# qPCR_pcb_module_array_led.net
KiCad netlist of a schematic drawn in EAGLE
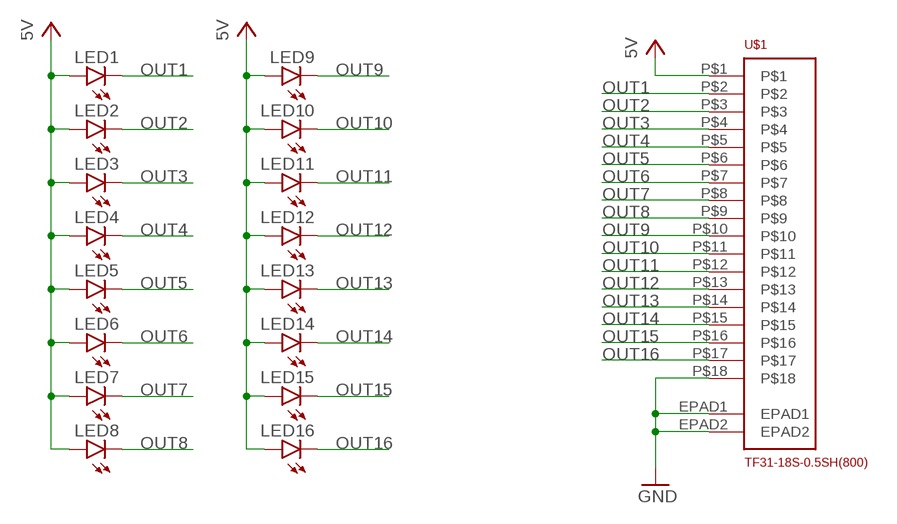
[diagram p0: schematic, sheet 1]

(export (version "E")
  (design (tool "Eeschema 10.0.6"))
  (components
    (comp (ref "LED1")
      (value "LED5MM")
      (footprint "eagle-import:LED5MM")
      (libsource (lib "eagle-import") (part "LED5MM"))
    )
    (comp (ref "LED2")
      (value "LED5MM")
      (footprint "eagle-import:LED5MM")
      (libsource (lib "eagle-import") (part "LED5MM"))
    )
    (comp (ref "LED3")
      (value "LED5MM")
      (footprint "eagle-import:LED5MM")
      (libsource (lib "eagle-import") (part "LED5MM"))
    )
    (comp (ref "LED4")
      (value "LED5MM")
      (footprint "eagle-import:LED5MM")
      (libsource (lib "eagle-import") (part "LED5MM"))
    )
    (comp (ref "LED5")
      (value "LED5MM")
      (footprint "eagle-import:LED5MM")
      (libsource (lib "eagle-import") (part "LED5MM"))
    )
    (comp (ref "LED6")
      (value "LED5MM")
      (footprint "eagle-import:LED5MM")
      (libsource (lib "eagle-import") (part "LED5MM"))
    )
    (comp (ref "LED7")
      (value "LED5MM")
      (footprint "eagle-import:LED5MM")
      (libsource (lib "eagle-import") (part "LED5MM"))
    )
    (comp (ref "LED8")
      (value "LED5MM")
      (footprint "eagle-import:LED5MM")
      (libsource (lib "eagle-import") (part "LED5MM"))
    )
    (comp (ref "LED9")
      (value "LED5MM")
      (footprint "eagle-import:LED5MM")
      (libsource (lib "eagle-import") (part "LED5MM"))
    )
    (comp (ref "LED10")
      (value "LED5MM")
      (footprint "eagle-import:LED5MM")
      (libsource (lib "eagle-import") (part "LED5MM"))
    )
    (comp (ref "LED11")
      (value "LED5MM")
      (footprint "eagle-import:LED5MM")
      (libsource (lib "eagle-import") (part "LED5MM"))
    )
    (comp (ref "LED12")
      (value "LED5MM")
      (footprint "eagle-import:LED5MM")
      (libsource (lib "eagle-import") (part "LED5MM"))
    )
    (comp (ref "LED13")
      (value "LED5MM")
      (footprint "eagle-import:LED5MM")
      (libsource (lib "eagle-import") (part "LED5MM"))
    )
    (comp (ref "LED14")
      (value "LED5MM")
      (footprint "eagle-import:LED5MM")
      (libsource (lib "eagle-import") (part "LED5MM"))
    )
    (comp (ref "LED15")
      (value "LED5MM")
      (footprint "eagle-import:LED5MM")
      (libsource (lib "eagle-import") (part "LED5MM"))
    )
    (comp (ref "LED16")
      (value "LED5MM")
      (footprint "eagle-import:LED5MM")
      (libsource (lib "eagle-import") (part "LED5MM"))
    )
    (comp (ref "U$1")
      (value "TF31-18S-0.5SH(800)")
      (footprint "eagle-import:TF31-18S-0.5SH(800)")
      (libsource (lib "eagle-import") (part "TF31-18S-0.5SH(800)"))
    )
  )
  (nets
    (net (code "1") (name "/OUT1") (class "Default")
      (node (ref "LED1") (pin "K") (pinfunction "C_K") (pintype "passive"))
      (node (ref "U$1") (pin "P$2") (pinfunction "P$2_P$2") (pintype "bidirectional"))
    )
    (net (code "2") (name "/OUT2") (class "Default")
      (node (ref "LED2") (pin "K") (pinfunction "C_K") (pintype "passive"))
      (node (ref "U$1") (pin "P$3") (pinfunction "P$3_P$3") (pintype "bidirectional"))
    )
    (net (code "3") (name "/OUT3") (class "Default")
      (node (ref "LED3") (pin "K") (pinfunction "C_K") (pintype "passive"))
      (node (ref "U$1") (pin "P$4") (pinfunction "P$4_P$4") (pintype "bidirectional"))
    )
    (net (code "4") (name "/OUT4") (class "Default")
      (node (ref "LED4") (pin "K") (pinfunction "C_K") (pintype "passive"))
      (node (ref "U$1") (pin "P$5") (pinfunction "P$5_P$5") (pintype "bidirectional"))
    )
    (net (code "5") (name "/OUT5") (class "Default")
      (node (ref "LED5") (pin "K") (pinfunction "C_K") (pintype "passive"))
      (node (ref "U$1") (pin "P$6") (pinfunction "P$6_P$6") (pintype "bidirectional"))
    )
    (net (code "6") (name "/OUT6") (class "Default")
      (node (ref "LED6") (pin "K") (pinfunction "C_K") (pintype "passive"))
      (node (ref "U$1") (pin "P$7") (pinfunction "P$7_P$7") (pintype "bidirectional"))
    )
    (net (code "7") (name "/OUT7") (class "Default")
      (node (ref "LED7") (pin "K") (pinfunction "C_K") (pintype "passive"))
      (node (ref "U$1") (pin "P$8") (pinfunction "P$8_P$8") (pintype "bidirectional"))
    )
    (net (code "8") (name "/OUT8") (class "Default")
      (node (ref "LED8") (pin "K") (pinfunction "C_K") (pintype "passive"))
      (node (ref "U$1") (pin "P$9") (pinfunction "P$9_P$9") (pintype "bidirectional"))
    )
    (net (code "9") (name "/OUT9") (class "Default")
      (node (ref "LED9") (pin "K") (pinfunction "C_K") (pintype "passive"))
      (node (ref "U$1") (pin "P$10") (pinfunction "P$10_P$10") (pintype "bidirectional"))
    )
    (net (code "10") (name "/OUT10") (class "Default")
      (node (ref "LED10") (pin "K") (pinfunction "C_K") (pintype "passive"))
      (node (ref "U$1") (pin "P$11") (pinfunction "P$11_P$11") (pintype "bidirectional"))
    )
    (net (code "11") (name "/OUT11") (class "Default")
      (node (ref "LED11") (pin "K") (pinfunction "C_K") (pintype "passive"))
      (node (ref "U$1") (pin "P$12") (pinfunction "P$12_P$12") (pintype "bidirectional"))
    )
    (net (code "12") (name "/OUT12") (class "Default")
      (node (ref "LED12") (pin "K") (pinfunction "C_K") (pintype "passive"))
      (node (ref "U$1") (pin "P$13") (pinfunction "P$13_P$13") (pintype "bidirectional"))
    )
    (net (code "13") (name "/OUT13") (class "Default")
      (node (ref "LED13") (pin "K") (pinfunction "C_K") (pintype "passive"))
      (node (ref "U$1") (pin "P$14") (pinfunction "P$14_P$14") (pintype "bidirectional"))
    )
    (net (code "14") (name "/OUT14") (class "Default")
      (node (ref "LED14") (pin "K") (pinfunction "C_K") (pintype "passive"))
      (node (ref "U$1") (pin "P$15") (pinfunction "P$15_P$15") (pintype "bidirectional"))
    )
    (net (code "15") (name "/OUT15") (class "Default")
      (node (ref "LED15") (pin "K") (pinfunction "C_K") (pintype "passive"))
      (node (ref "U$1") (pin "P$16") (pinfunction "P$16_P$16") (pintype "bidirectional"))
    )
    (net (code "16") (name "/OUT16") (class "Default")
      (node (ref "LED16") (pin "K") (pinfunction "C_K") (pintype "passive"))
      (node (ref "U$1") (pin "P$17") (pinfunction "P$17_P$17") (pintype "bidirectional"))
    )
    (net (code "17") (name "5V") (class "Default")
      (node (ref "LED1") (pin "A") (pinfunction "A_A") (pintype "passive"))
      (node (ref "LED10") (pin "A") (pinfunction "A_A") (pintype "passive"))
      (node (ref "LED11") (pin "A") (pinfunction "A_A") (pintype "passive"))
      (node (ref "LED12") (pin "A") (pinfunction "A_A") (pintype "passive"))
      (node (ref "LED13") (pin "A") (pinfunction "A_A") (pintype "passive"))
      (node (ref "LED14") (pin "A") (pinfunction "A_A") (pintype "passive"))
      (node (ref "LED15") (pin "A") (pinfunction "A_A") (pintype "passive"))
      (node (ref "LED16") (pin "A") (pinfunction "A_A") (pintype "passive"))
      (node (ref "LED2") (pin "A") (pinfunction "A_A") (pintype "passive"))
      (node (ref "LED3") (pin "A") (pinfunction "A_A") (pintype "passive"))
      (node (ref "LED4") (pin "A") (pinfunction "A_A") (pintype "passive"))
      (node (ref "LED5") (pin "A") (pinfunction "A_A") (pintype "passive"))
      (node (ref "LED6") (pin "A") (pinfunction "A_A") (pintype "passive"))
      (node (ref "LED7") (pin "A") (pinfunction "A_A") (pintype "passive"))
      (node (ref "LED8") (pin "A") (pinfunction "A_A") (pintype "passive"))
      (node (ref "LED9") (pin "A") (pinfunction "A_A") (pintype "passive"))
      (node (ref "U$1") (pin "P$1") (pinfunction "P$1_P$1") (pintype "bidirectional"))
    )
    (net (code "18") (name "GND") (class "Default")
      (node (ref "U$1") (pin "EPAD1") (pinfunction "EPAD1_EPAD1") (pintype "bidirectional"))
      (node (ref "U$1") (pin "EPAD2") (pinfunction "EPAD2_EPAD2") (pintype "bidirectional"))
      (node (ref "U$1") (pin "P$18") (pinfunction "P$18_P$18") (pintype "bidirectional"))
    )
  )
)
